# sche_out.net
KiCad netlist of a schematic drawn in Altium Designer
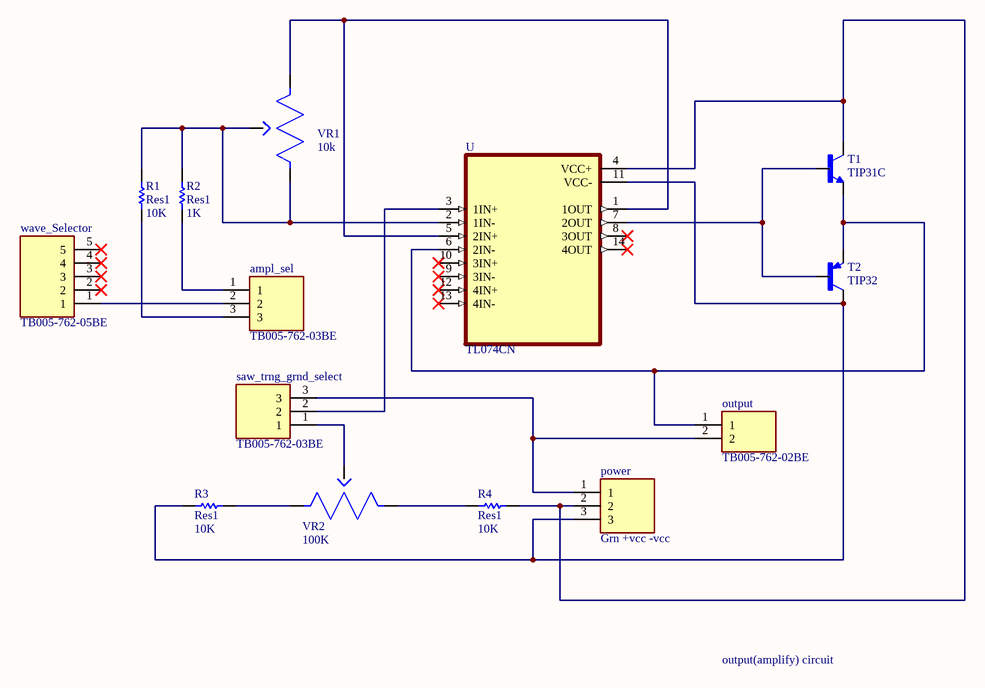
[diagram p0: sche_out.SchDoc]

(export (version "E")
  (design (tool "Eeschema 10.0.6"))
  (components
    (comp (ref "ampl_sel")
      (value "TB005-762-03BE")
      (footprint "CUI_TB005-762-03BE")
      (description "2~24 Poles, Screw Type, Horizontal, 7.62 Pitch, 26~10 _AWG_, Terminal Block Connector")
      (fields (field (name "MF") "CUI Devices"))
      (libsource (lib "") (part "TB005-762-03BE_1"))
    )
    (comp (ref "output")
      (value "TB005-762-02BE")
      (footprint "CUI_TB005-762-02BE")
      (description "2~24 Poles, Screw Type, Horizontal, 7.62 Pitch, 26~10 _AWG_, Terminal Block Connector")
      (fields (field (name "MF") "CUI Devices"))
      (libsource (lib "TB005-762-02BE") (part "TB005-762-02BE"))
    )
    (comp (ref "power")
      (value "Grn +vcc -vcc")
      (footprint "CUI_TB005-762-03BE")
      (description "2~24 Poles, Screw Type, Horizontal, 7.62 Pitch, 26~10 _AWG_, Terminal Block Connector")
      (fields (field (name "MP") "TB005-762-03BE") (field (name "MF") "CUI Devices"))
      (libsource (lib "") (part "TB005-762-03BE_1"))
    )
    (comp (ref "R1")
      (value "Res1")
      (footprint "AXIAL-0.3")
      (description "Resistor")
      (fields (field (name "ALTIUM_VALUE") "10K") (field (name "PUBLISHER") "Altium Limited"))
      (libsource (lib "Miscellaneous Devices") (part "Res1"))
    )
    (comp (ref "R2")
      (value "Res1")
      (footprint "AXIAL-0.3")
      (description "Resistor")
      (fields (field (name "ALTIUM_VALUE") "1K") (field (name "PUBLISHER") "Altium Limited"))
      (libsource (lib "Miscellaneous Devices") (part "Res1"))
    )
    (comp (ref "R3")
      (value "Res1")
      (footprint "AXIAL-0.3")
      (description "Resistor")
      (fields (field (name "ALTIUM_VALUE") "10K") (field (name "PUBLISHER") "Altium Limited"))
      (libsource (lib "Miscellaneous Devices") (part "Res1"))
    )
    (comp (ref "R4")
      (value "Res1")
      (footprint "AXIAL-0.3")
      (description "Resistor")
      (fields (field (name "ALTIUM_VALUE") "10K") (field (name "PUBLISHER") "Altium Limited"))
      (libsource (lib "Miscellaneous Devices") (part "Res1"))
    )
    (comp (ref "saw_trng_grnd_select")
      (value "TB005-762-03BE")
      (footprint "CUI_TB005-762-03BE")
      (description "2~24 Poles, Screw Type, Horizontal, 7.62 Pitch, 26~10 _AWG_, Terminal Block Connector")
      (fields (field (name "MF") "CUI Devices"))
      (libsource (lib "TB005-762-03BE") (part "TB005-762-03BE"))
    )
    (comp (ref "T1")
      (value "TIP31C")
      (footprint "TO220")
      (description "Bipolar _BJT_ Transistor NPN 100V 3A 3MHz 2W Through Hole TO-220AB")
      (fields (field (name "MF") "Renesas Electronics"))
      (libsource (lib "TIP31C") (part "TIP31C"))
    )
    (comp (ref "T2")
      (value "TIP32")
      (footprint "TO220")
      (description "Bipolar _BJT_ Transistor PNP 40V 3A 3MHz 2W Through Hole TO-220-3")
      (fields (field (name "MF") "ON Semiconductor"))
      (libsource (lib "TIP32") (part "TIP32"))
    )
    (comp (ref "U")
      (value "TL074CN")
      (footprint "DIP794W45P254L1969H508Q14")
      (description "Quad Low-Noise JFET-Input General-Purpose Operational Amplifier 14-PDIP 0 to 70")
      (fields (field (name "MF") "Texas Instruments"))
      (libsource (lib "TL074CN") (part "TL074CN"))
    )
    (comp (ref "VR1")
      (value "10k")
      (footprint "P160")
      (description "500k Ohm 1 Gang Linear Panel Mount Potentiometer None 1 Turn Conductive Plastic 0.2W, 1/5W PC Pins")
      (fields (field (name "MF") "TT Electronics/BI") (field (name "DIGI-KEY_PART_NUMBER") "987-1304-ND"))
      (libsource (lib "P160KN-0QC15B500K") (part "P160KN-0QC15B500K"))
    )
    (comp (ref "VR2")
      (value "100K")
      (footprint "P160")
      (description "500k Ohm 1 Gang Linear Panel Mount Potentiometer None 1 Turn Conductive Plastic 0.2W, 1/5W PC Pins")
      (fields (field (name "MF") "TT Electronics/BI") (field (name "DIGI-KEY_PART_NUMBER") "987-1304-ND"))
      (libsource (lib "P160KN-0QC15B500K") (part "P160KN-0QC15B500K"))
    )
    (comp (ref "wave_Selector")
      (value "TB005-762-05BE")
      (footprint "CUI_TB005-762-05BE")
      (description "2~24 Poles, Screw Type, Horizontal, 7.62 Pitch, 26~10 (AWG), Terminal Block Connector")
      (fields (field (name "MF") "CUI Devices"))
      (libsource (lib "TB005-762-05BE") (part "TB005-762-05BE"))
    )
  )
  (nets
    (net (code "1") (name "Net-(R1-Pad1)") (class "Default")
      (node (ref "R1") (pin "1") (pinfunction "1_1") (pintype "passive"))
      (node (ref "ampl_sel") (pin "3") (pinfunction "3_3") (pintype "passive"))
    )
    (net (code "2") (name "Net-(R2-Pad1)") (class "Default")
      (node (ref "R2") (pin "1") (pinfunction "1_1") (pintype "passive"))
      (node (ref "ampl_sel") (pin "1") (pinfunction "1_1") (pintype "passive"))
    )
    (net (code "3") (name "Net-(R3-Pad2)") (class "Default")
      (node (ref "R3") (pin "2") (pinfunction "2_2") (pintype "passive"))
      (node (ref "VR2") (pin "3") (pinfunction "3_3") (pintype "bidirectional"))
    )
    (net (code "4") (name "Net-(R4-Pad1)") (class "Default")
      (node (ref "R4") (pin "1") (pinfunction "1_1") (pintype "passive"))
      (node (ref "VR2") (pin "1") (pinfunction "1_1") (pintype "bidirectional"))
    )
    (net (code "5") (name "Net-(T1-B)") (class "Default")
      (node (ref "T1") (pin "1") (pinfunction "B_1") (pintype "passive"))
      (node (ref "T2") (pin "1") (pinfunction "B_1") (pintype "passive"))
      (node (ref "U") (pin "7") (pinfunction "2OUT_7") (pintype "output"))
    )
    (net (code "6") (name "Net-(T1-C)") (class "Default")
      (node (ref "R4") (pin "2") (pinfunction "2_2") (pintype "passive"))
      (node (ref "T1") (pin "2") (pinfunction "C_2") (pintype "passive"))
      (node (ref "U") (pin "4") (pinfunction "VCC+_4") (pintype "power_in"))
      (node (ref "power") (pin "2") (pinfunction "2_2") (pintype "passive"))
    )
    (net (code "7") (name "Net-(T1-E)") (class "Default")
      (node (ref "T1") (pin "3") (pinfunction "E_3") (pintype "passive"))
      (node (ref "T2") (pin "3") (pinfunction "E_3") (pintype "passive"))
      (node (ref "U") (pin "6") (pinfunction "2IN-_6") (pintype "input"))
      (node (ref "output") (pin "1") (pinfunction "1_1") (pintype "passive"))
    )
    (net (code "8") (name "Net-(T2-C)") (class "Default")
      (node (ref "R3") (pin "1") (pinfunction "1_1") (pintype "passive"))
      (node (ref "T2") (pin "2") (pinfunction "C_2") (pintype "passive"))
      (node (ref "U") (pin "11") (pinfunction "VCC-_11") (pintype "power_in"))
      (node (ref "power") (pin "3") (pinfunction "3_3") (pintype "passive"))
    )
    (net (code "9") (name "Net-(U-1IN+)") (class "Default")
      (node (ref "U") (pin "3") (pinfunction "1IN+_3") (pintype "input"))
      (node (ref "saw_trng_grnd_select") (pin "2") (pinfunction "2_2") (pintype "passive"))
    )
    (net (code "10") (name "Net-(U-1IN-)") (class "Default")
      (node (ref "R1") (pin "2") (pinfunction "2_2") (pintype "passive"))
      (node (ref "R2") (pin "2") (pinfunction "2_2") (pintype "passive"))
      (node (ref "U") (pin "2") (pinfunction "1IN-_2") (pintype "input"))
      (node (ref "VR1") (pin "2") (pinfunction "2_2") (pintype "bidirectional"))
      (node (ref "VR1") (pin "3") (pinfunction "3_3") (pintype "bidirectional"))
    )
    (net (code "11") (name "Net-(U-1OUT)") (class "Default")
      (node (ref "U") (pin "1") (pinfunction "1OUT_1") (pintype "output"))
      (node (ref "U") (pin "5") (pinfunction "2IN+_5") (pintype "input"))
      (node (ref "VR1") (pin "1") (pinfunction "1_1") (pintype "bidirectional"))
    )
    (net (code "12") (name "Net-(VR2-Pad2)") (class "Default")
      (node (ref "VR2") (pin "2") (pinfunction "2_2") (pintype "bidirectional"))
      (node (ref "saw_trng_grnd_select") (pin "1") (pinfunction "1_1") (pintype "passive"))
    )
    (net (code "13") (name "Net-(ampl_sel-Pad2)") (class "Default")
      (node (ref "ampl_sel") (pin "2") (pinfunction "2_2") (pintype "passive"))
      (node (ref "wave_Selector") (pin "1") (pinfunction "1_1") (pintype "passive"))
    )
    (net (code "14") (name "Net-(output-Pad2)") (class "Default")
      (node (ref "output") (pin "2") (pinfunction "2_2") (pintype "passive"))
      (node (ref "power") (pin "1") (pinfunction "1_1") (pintype "passive"))
      (node (ref "saw_trng_grnd_select") (pin "3") (pinfunction "3_3") (pintype "passive"))
    )
    (net (code "15") (name "unconnected-(U-3IN+-Pad10)") (class "Default")
      (node (ref "U") (pin "10") (pinfunction "3IN+_10") (pintype "input+no_connect"))
    )
    (net (code "16") (name "unconnected-(U-3IN--Pad9)") (class "Default")
      (node (ref "U") (pin "9") (pinfunction "3IN-_9") (pintype "input+no_connect"))
    )
    (net (code "17") (name "unconnected-(U-3OUT-Pad8)") (class "Default")
      (node (ref "U") (pin "8") (pinfunction "3OUT_8") (pintype "output+no_connect"))
    )
    (net (code "18") (name "unconnected-(U-4IN+-Pad12)") (class "Default")
      (node (ref "U") (pin "12") (pinfunction "4IN+_12") (pintype "input+no_connect"))
    )
    (net (code "19") (name "unconnected-(U-4IN--Pad13)") (class "Default")
      (node (ref "U") (pin "13") (pinfunction "4IN-_13") (pintype "input+no_connect"))
    )
    (net (code "20") (name "unconnected-(U-4OUT-Pad14)") (class "Default")
      (node (ref "U") (pin "14") (pinfunction "4OUT_14") (pintype "output+no_connect"))
    )
    (net (code "21") (name "unconnected-(wave_Selector-Pad2)") (class "Default")
      (node (ref "wave_Selector") (pin "2") (pinfunction "2_2") (pintype "passive+no_connect"))
    )
    (net (code "22") (name "unconnected-(wave_Selector-Pad3)") (class "Default")
      (node (ref "wave_Selector") (pin "3") (pinfunction "3_3") (pintype "passive+no_connect"))
    )
    (net (code "23") (name "unconnected-(wave_Selector-Pad4)") (class "Default")
      (node (ref "wave_Selector") (pin "4") (pinfunction "4_4") (pintype "passive+no_connect"))
    )
    (net (code "24") (name "unconnected-(wave_Selector-Pad5)") (class "Default")
      (node (ref "wave_Selector") (pin "5") (pinfunction "5_5") (pintype "passive+no_connect"))
    )
  )
)
